# USB_Power_Switcher.net
KiCad netlist of a schematic drawn in EAGLE
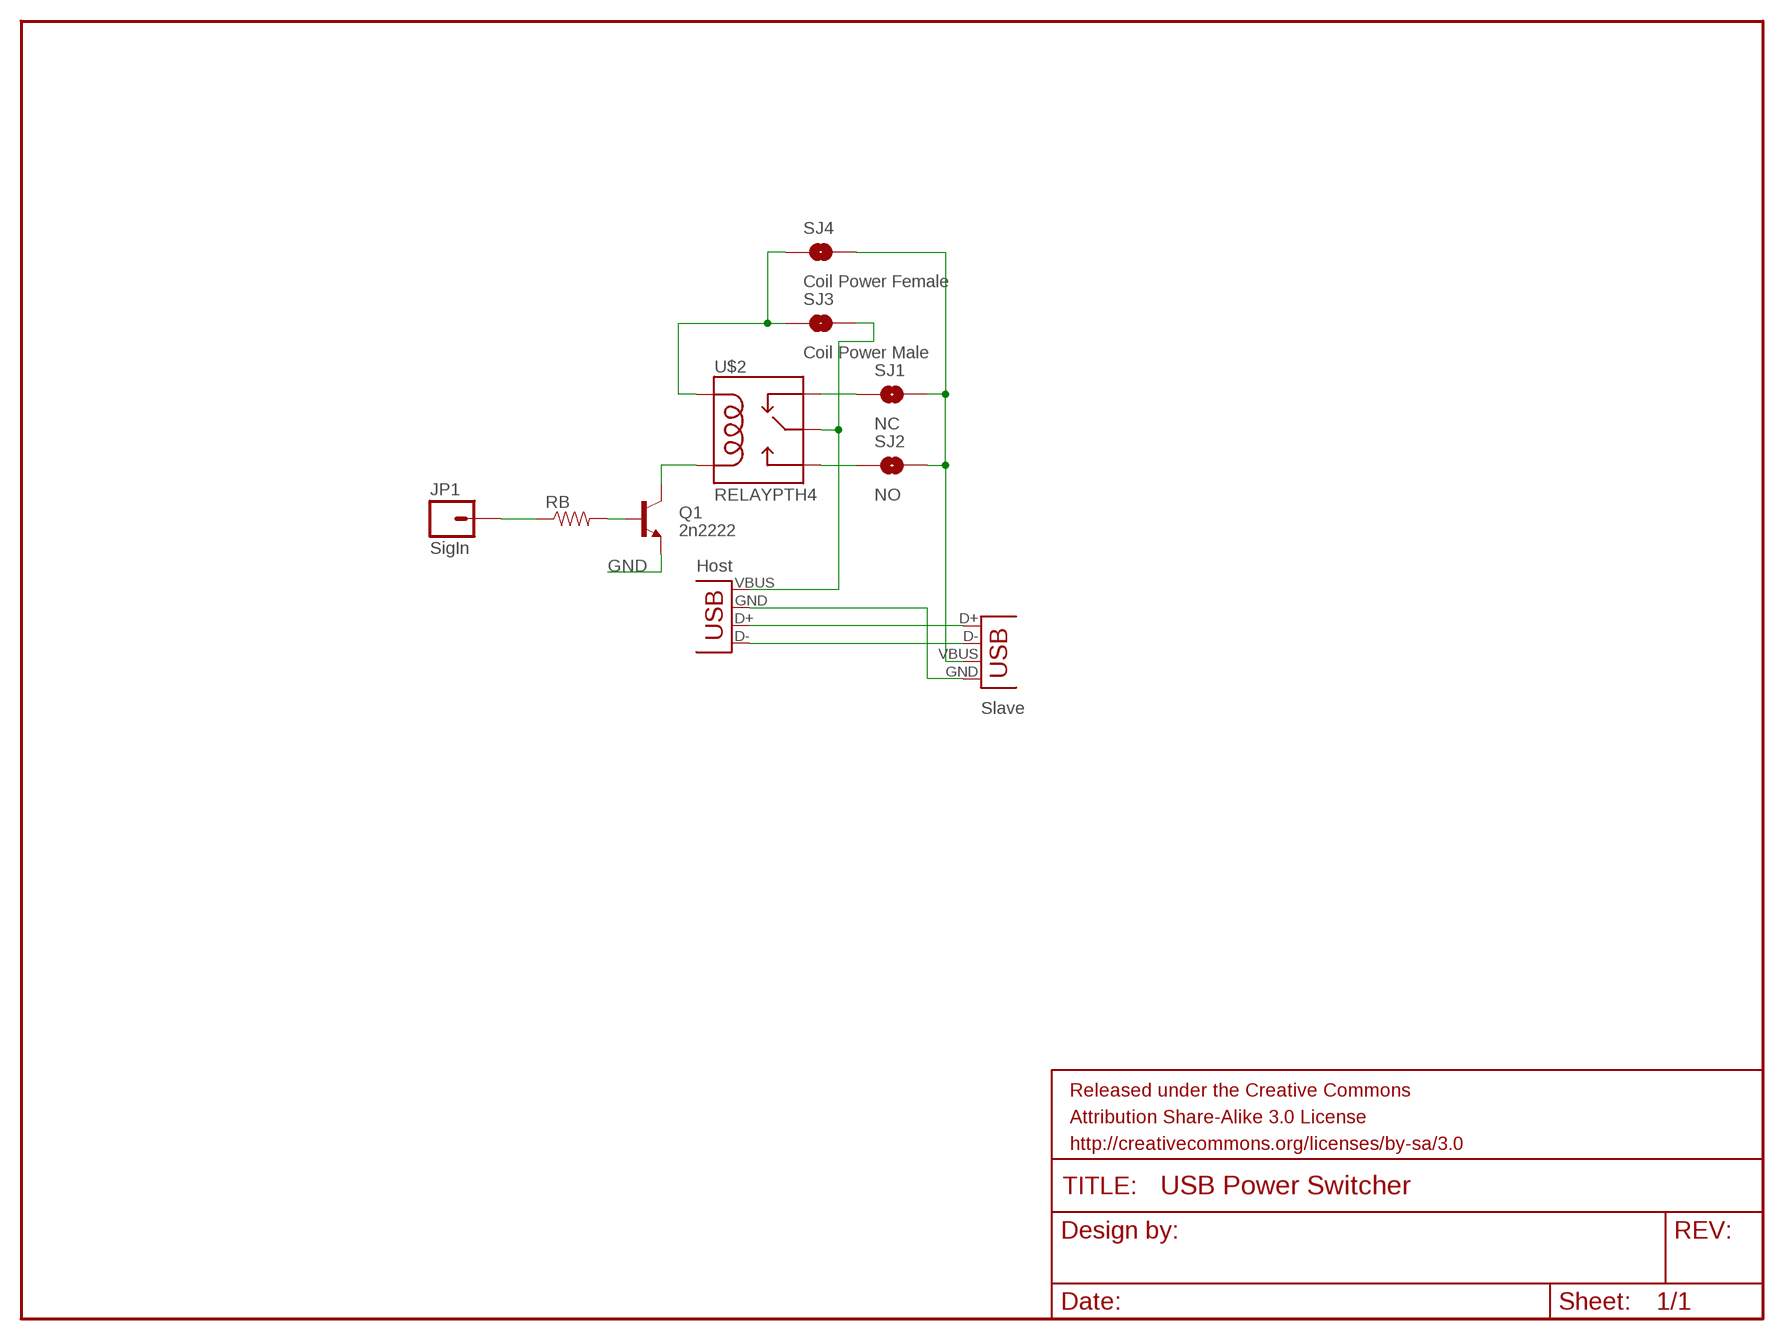
[diagram p0: schematic, sheet 1]

(export (version "E")
  (design (tool "Eeschema 10.0.6"))
  (components
    (comp (ref "JP1")
      (value "SigIn")
      (footprint "eagle-import:1X01")
      (libsource (lib "eagle-import") (part "M01PTH"))
    )
    (comp (ref "Q1")
      (value "2n2222")
      (footprint "eagle-import:TO-92-AMMO")
      (libsource (lib "eagle-import") (part "TRANSISTOR_NPNTO-92-AMMO"))
    )
    (comp (ref "RB")
      (value "RESISTORAXIAL-0.3")
      (footprint "eagle-import:AXIAL-0.3")
      (libsource (lib "eagle-import") (part "RESISTORAXIAL-0.3"))
    )
    (comp (ref "SJ1")
      (value "NC")
      (footprint "eagle-import:SJ_2S_BIG")
      (libsource (lib "eagle-import") (part "SOLDERJUMPERBIGNC"))
    )
    (comp (ref "SJ2")
      (value "NO")
      (footprint "eagle-import:SJ_2S_BIG")
      (libsource (lib "eagle-import") (part "SOLDERJUMPERBIGNC"))
    )
    (comp (ref "SJ3")
      (value "Coil Power Male")
      (footprint "eagle-import:SJ_2S-NO")
      (libsource (lib "eagle-import") (part "SOLDERJUMPERNO"))
    )
    (comp (ref "SJ4")
      (value "Coil Power Female")
      (footprint "eagle-import:SJ_2S-NO")
      (libsource (lib "eagle-import") (part "SOLDERJUMPERNO"))
    )
    (comp (ref "U$2")
      (value "RELAYPTH4")
      (footprint "eagle-import:RELAY-JZC")
      (libsource (lib "eagle-import") (part "RELAYPTH4"))
    )
    (comp (ref "X1")
      (value "USB-A-SMD")
      (footprint "eagle-import:USB-A-S-NOSILK-FEMALE")
      (libsource (lib "eagle-import") (part "USB-A-SMD"))
    )
    (comp (ref "X2")
      (value "USB-A-H")
      (footprint "eagle-import:USB-A-H")
      (libsource (lib "eagle-import") (part "USB-A-H"))
    )
  )
  (nets
    (net (code "1") (name "/GND") (class "Default")
      (node (ref "Q1") (pin "1") (pinfunction "E_1") (pintype "passive"))
      (node (ref "X1") (pin "GND") (pinfunction "GND_GND") (pintype "bidirectional"))
      (node (ref "X2") (pin "GND") (pinfunction "VBUS_GND") (pintype "bidirectional"))
    )
    (net (code "2") (name "Net-(Q1-B)") (class "Default")
      (node (ref "Q1") (pin "2") (pinfunction "B_2") (pintype "passive"))
      (node (ref "RB") (pin "P$2") (pinfunction "2_P$2") (pintype "passive"))
    )
    (net (code "3") (name "Net-(Q1-C)") (class "Default")
      (node (ref "Q1") (pin "3") (pinfunction "C_3") (pintype "passive"))
      (node (ref "U$2") (pin "1") (pinfunction "COIL2_1") (pintype "bidirectional"))
    )
    (net (code "4") (name "Net-(RB-1)") (class "Default")
      (node (ref "JP1") (pin "1") (pinfunction "1_1") (pintype "passive"))
      (node (ref "RB") (pin "P$1") (pinfunction "1_P$1") (pintype "passive"))
    )
    (net (code "5") (name "Net-(SJ1-Pad2)") (class "Default")
      (node (ref "SJ1") (pin "2") (pinfunction "2_2") (pintype "passive"))
      (node (ref "SJ2") (pin "2") (pinfunction "2_2") (pintype "passive"))
      (node (ref "SJ4") (pin "2") (pinfunction "2_2") (pintype "passive"))
      (node (ref "X1") (pin "VBUS") (pinfunction "VBUS_VBUS") (pintype "bidirectional"))
    )
    (net (code "6") (name "Net-(U$2-COIL1)") (class "Default")
      (node (ref "SJ3") (pin "1") (pinfunction "1_1") (pintype "passive"))
      (node (ref "SJ4") (pin "1") (pinfunction "1_1") (pintype "passive"))
      (node (ref "U$2") (pin "5") (pinfunction "COIL1_5") (pintype "bidirectional"))
    )
    (net (code "7") (name "Net-(U$2-MAIN)") (class "Default")
      (node (ref "SJ3") (pin "2") (pinfunction "2_2") (pintype "passive"))
      (node (ref "U$2") (pin "4") (pinfunction "MAIN_4") (pintype "bidirectional"))
      (node (ref "X2") (pin "VBUS") (pinfunction "GND_VBUS") (pintype "bidirectional"))
    )
    (net (code "8") (name "Net-(U$2-NC)") (class "Default")
      (node (ref "SJ1") (pin "1") (pinfunction "1_1") (pintype "passive"))
      (node (ref "U$2") (pin "2") (pinfunction "NC_2") (pintype "bidirectional"))
    )
    (net (code "9") (name "Net-(U$2-NO)") (class "Default")
      (node (ref "SJ2") (pin "1") (pinfunction "1_1") (pintype "passive"))
      (node (ref "U$2") (pin "3") (pinfunction "NO_3") (pintype "bidirectional"))
    )
    (net (code "10") (name "Net-(X2-D+)") (class "Default")
      (node (ref "X1") (pin "D-") (pinfunction "D-_D-") (pintype "bidirectional"))
      (node (ref "X2") (pin "D-") (pinfunction "D+_D-") (pintype "bidirectional"))
    )
    (net (code "11") (name "Net-(X2-D-)") (class "Default")
      (node (ref "X1") (pin "D+") (pinfunction "D+_D+") (pintype "bidirectional"))
      (node (ref "X2") (pin "D+") (pinfunction "D-_D+") (pintype "bidirectional"))
    )
  )
)
